# Teensy_FrequencyShield_2ch_slim.net
KiCad netlist of a schematic drawn in EAGLE
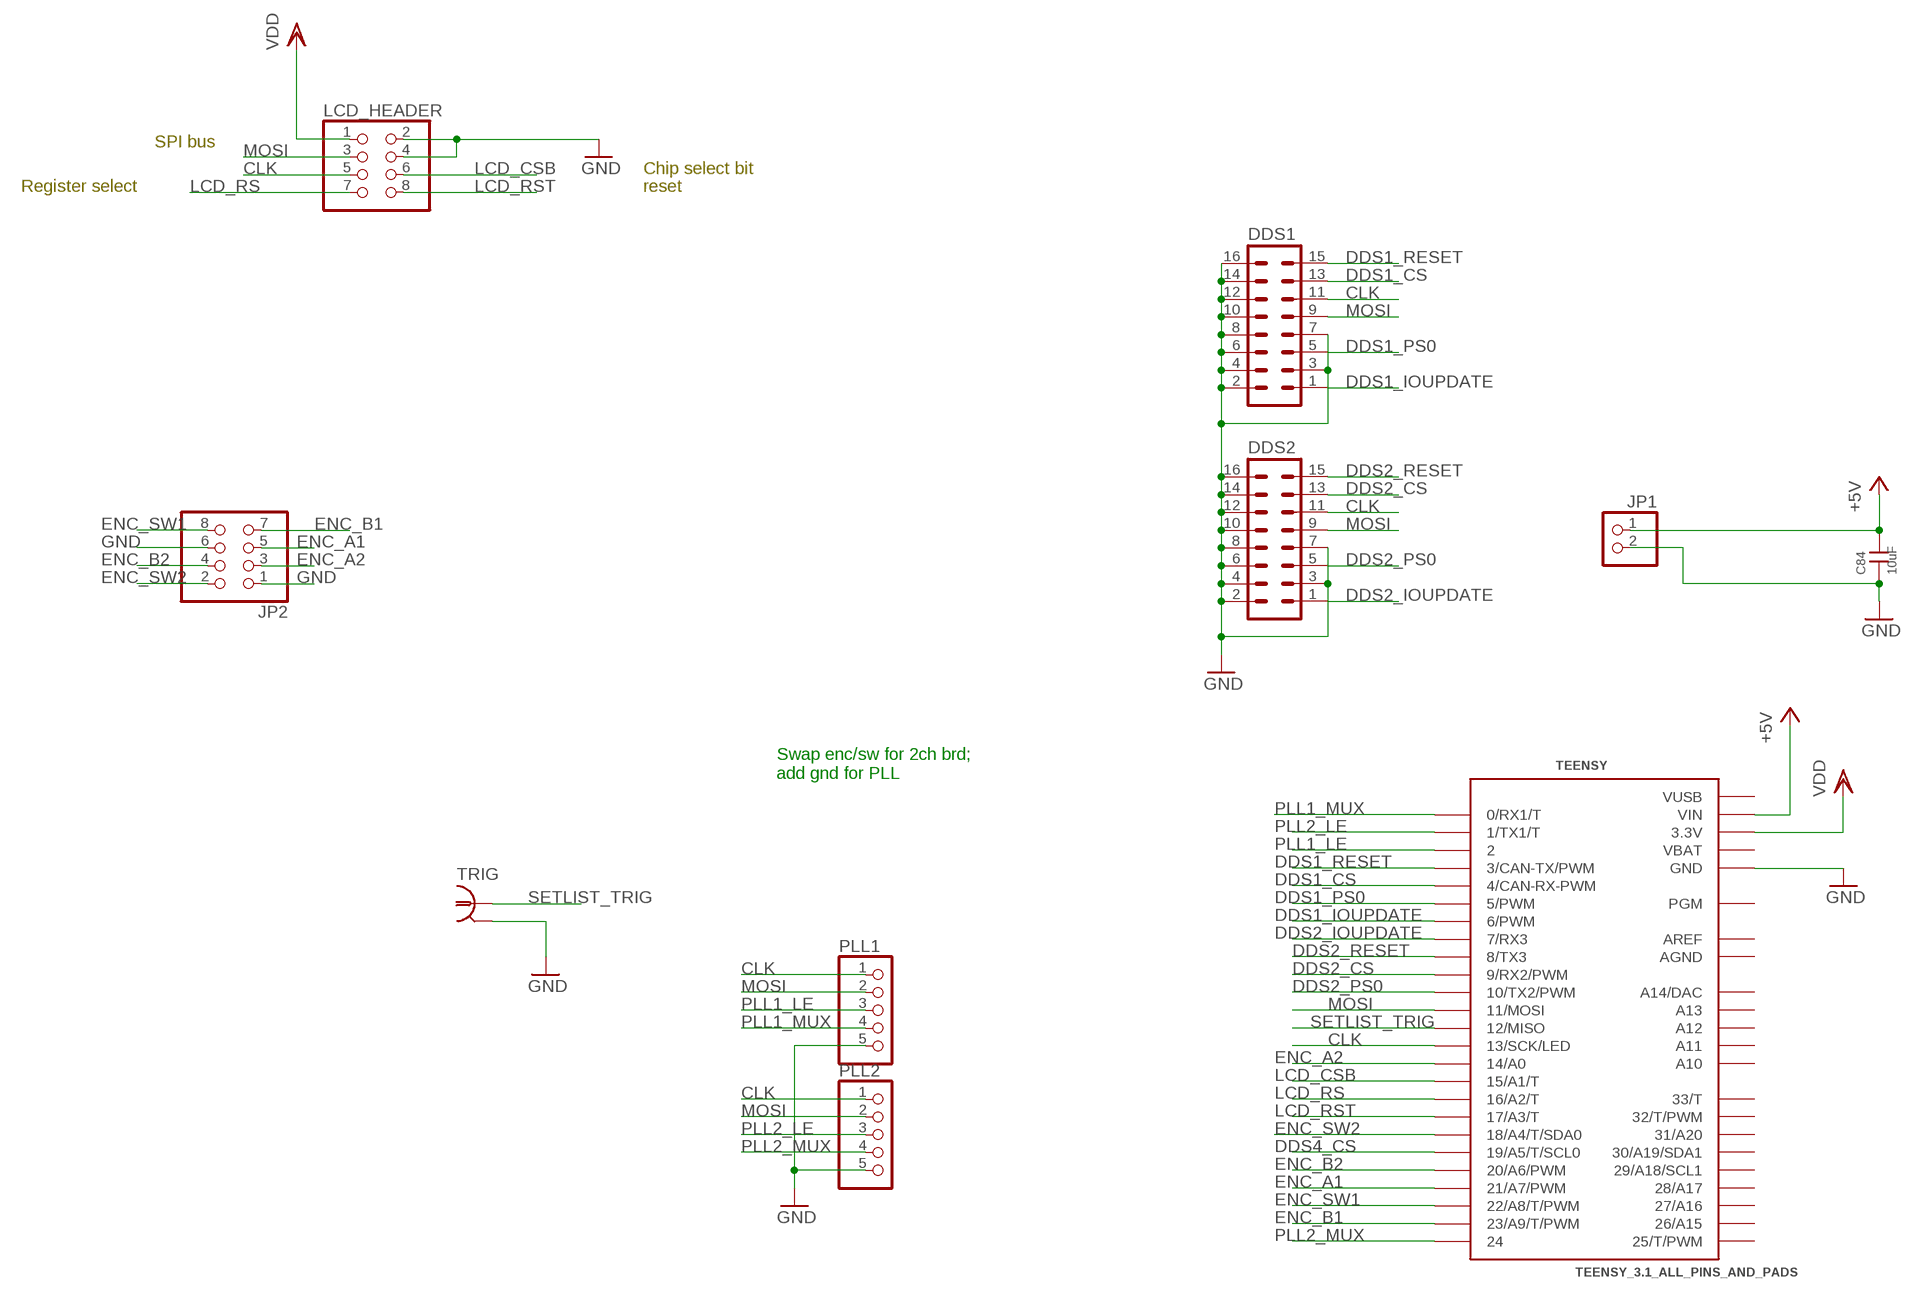
[diagram p0: schematic, sheet 1]

(export (version "E")
  (design (tool "Eeschema 10.0.6"))
  (components
    (comp (ref "C84")
      (value "10uF")
      (footprint "eagle-import:0805")
      (fields (field (name "PARTNO") "1276-2890-1-ND"))
      (libsource (lib "eagle-import") (part "CAP0805"))
    )
    (comp (ref "DDS1")
      (value "ML16")
      (footprint "eagle-import:ML16")
      (libsource (lib "eagle-import") (part "ML16"))
    )
    (comp (ref "DDS2")
      (value "ML16")
      (footprint "eagle-import:ML16")
      (libsource (lib "eagle-import") (part "ML16"))
    )
    (comp (ref "JP1")
      (value "PINHD-1X2")
      (footprint "eagle-import:1X02")
      (libsource (lib "eagle-import") (part "PINHD-1X2"))
    )
    (comp (ref "JP2")
      (value "PINHD-2X4-SHROUD")
      (footprint "eagle-import:ML08")
      (libsource (lib "eagle-import") (part "PINHD-2X4-SHROUD"))
    )
    (comp (ref "LCD_HEADER")
      (value "PINHD-2X4-SHROUD")
      (footprint "eagle-import:ML08")
      (libsource (lib "eagle-import") (part "PINHD-2X4-SHROUD"))
    )
    (comp (ref "PLL1")
      (value "PINHD-1X5")
      (footprint "eagle-import:1X05")
      (libsource (lib "eagle-import") (part "PINHD-1X5"))
    )
    (comp (ref "PLL2")
      (value "PINHD-1X5")
      (footprint "eagle-import:1X05")
      (libsource (lib "eagle-import") (part "PINHD-1X5"))
    )
    (comp (ref "TEENSY")
      (value "TEENSY_3.1_ALL_PINS_AND_PADS")
      (footprint "eagle-import:TEENSY_3.1_ALLPINS")
      (libsource (lib "eagle-import") (part "TEENSY_3.1_ALL_PINS_AND_PADS"))
    )
    (comp (ref "TRIG")
      (value "BNC-H")
      (footprint "eagle-import:BNC90")
      (libsource (lib "eagle-import") (part "BNC-H"))
    )
  )
  (nets
    (net (code "1") (name "+5V") (class "Default")
      (node (ref "C84") (pin "2") (pinfunction "P$2_2") (pintype "passive"))
      (node (ref "JP1") (pin "1") (pinfunction "1_1") (pintype "passive"))
      (node (ref "TEENSY") (pin "VIN") (pinfunction "VIN_VIN") (pintype "power_in"))
    )
    (net (code "2") (name "/AGND") (class "Default")
      (node (ref "TEENSY") (pin "AGND") (pinfunction "AGND_AGND") (pintype "power_in"))
    )
    (net (code "3") (name "/AREF") (class "Default")
      (node (ref "TEENSY") (pin "AREF") (pinfunction "AREF_AREF") (pintype "power_in"))
    )
    (net (code "4") (name "/CLK") (class "Default")
      (node (ref "DDS1") (pin "11") (pinfunction "11_11") (pintype "passive"))
      (node (ref "DDS2") (pin "11") (pinfunction "11_11") (pintype "passive"))
      (node (ref "LCD_HEADER") (pin "5") (pinfunction "5_5") (pintype "passive"))
      (node (ref "PLL1") (pin "1") (pinfunction "1_1") (pintype "passive"))
      (node (ref "PLL2") (pin "1") (pinfunction "1_1") (pintype "passive"))
      (node (ref "TEENSY") (pin "13") (pinfunction "13/SCK/LED_13") (pintype "bidirectional"))
    )
    (net (code "5") (name "/DDS1_CS") (class "Default")
      (node (ref "DDS1") (pin "13") (pinfunction "13_13") (pintype "passive"))
      (node (ref "TEENSY") (pin "4") (pinfunction "4/CAN-RX-PWM_4") (pintype "bidirectional"))
    )
    (net (code "6") (name "/DDS1_IOUPDATE") (class "Default")
      (node (ref "DDS1") (pin "1") (pinfunction "1_1") (pintype "passive"))
      (node (ref "TEENSY") (pin "6") (pinfunction "6/PWM_6") (pintype "bidirectional"))
    )
    (net (code "7") (name "/DDS1_PS0") (class "Default")
      (node (ref "DDS1") (pin "5") (pinfunction "5_5") (pintype "passive"))
      (node (ref "TEENSY") (pin "5") (pinfunction "5/PWM_5") (pintype "bidirectional"))
    )
    (net (code "8") (name "/DDS1_RESET") (class "Default")
      (node (ref "DDS1") (pin "15") (pinfunction "15_15") (pintype "passive"))
      (node (ref "TEENSY") (pin "3") (pinfunction "3/CAN-TX/PWM_3") (pintype "bidirectional"))
    )
    (net (code "9") (name "/DDS2_CS") (class "Default")
      (node (ref "DDS2") (pin "13") (pinfunction "13_13") (pintype "passive"))
      (node (ref "TEENSY") (pin "9") (pinfunction "9/RX2/PWM_9") (pintype "bidirectional"))
    )
    (net (code "10") (name "/DDS2_IOUPDATE") (class "Default")
      (node (ref "DDS2") (pin "1") (pinfunction "1_1") (pintype "passive"))
      (node (ref "TEENSY") (pin "7") (pinfunction "7/RX3_7") (pintype "bidirectional"))
    )
    (net (code "11") (name "/DDS2_PS0") (class "Default")
      (node (ref "DDS2") (pin "5") (pinfunction "5_5") (pintype "passive"))
      (node (ref "TEENSY") (pin "10") (pinfunction "10/TX2/PWM_10") (pintype "bidirectional"))
    )
    (net (code "12") (name "/DDS2_RESET") (class "Default")
      (node (ref "DDS2") (pin "15") (pinfunction "15_15") (pintype "passive"))
      (node (ref "TEENSY") (pin "8") (pinfunction "8/TX3_8") (pintype "bidirectional"))
    )
    (net (code "13") (name "/DDS4_CS") (class "Default")
      (node (ref "TEENSY") (pin "19/A5") (pinfunction "19/A5/T/SCL0_19/A5") (pintype "bidirectional"))
    )
    (net (code "14") (name "/ENC_A1") (class "Default")
      (node (ref "JP2") (pin "5") (pinfunction "5_5") (pintype "passive"))
      (node (ref "TEENSY") (pin "21/A7") (pinfunction "21/A7/PWM_21/A7") (pintype "bidirectional"))
    )
    (net (code "15") (name "/ENC_A2") (class "Default")
      (node (ref "JP2") (pin "3") (pinfunction "3_3") (pintype "passive"))
      (node (ref "TEENSY") (pin "14/A0") (pinfunction "14/A0_14/A0") (pintype "bidirectional"))
    )
    (net (code "16") (name "/ENC_B1") (class "Default")
      (node (ref "JP2") (pin "7") (pinfunction "7_7") (pintype "passive"))
      (node (ref "TEENSY") (pin "23/A9") (pinfunction "23/A9/T/PWM_23/A9") (pintype "bidirectional"))
    )
    (net (code "17") (name "/ENC_B2") (class "Default")
      (node (ref "JP2") (pin "4") (pinfunction "4_4") (pintype "passive"))
      (node (ref "TEENSY") (pin "20/A6") (pinfunction "20/A6/PWM_20/A6") (pintype "bidirectional"))
    )
    (net (code "18") (name "/ENC_SW1") (class "Default")
      (node (ref "JP2") (pin "8") (pinfunction "8_8") (pintype "passive"))
      (node (ref "TEENSY") (pin "22/A8") (pinfunction "22/A8/T/PWM_22/A8") (pintype "bidirectional"))
    )
    (net (code "19") (name "/ENC_SW2") (class "Default")
      (node (ref "JP2") (pin "2") (pinfunction "2_2") (pintype "passive"))
      (node (ref "TEENSY") (pin "18/A4") (pinfunction "18/A4/T/SDA0_18/A4") (pintype "bidirectional"))
    )
    (net (code "20") (name "/LCD_CSB") (class "Default")
      (node (ref "LCD_HEADER") (pin "6") (pinfunction "6_6") (pintype "passive"))
      (node (ref "TEENSY") (pin "15/A1") (pinfunction "15/A1/T_15/A1") (pintype "bidirectional"))
    )
    (net (code "21") (name "/LCD_RS") (class "Default")
      (node (ref "LCD_HEADER") (pin "7") (pinfunction "7_7") (pintype "passive"))
      (node (ref "TEENSY") (pin "16/A2") (pinfunction "16/A2/T_16/A2") (pintype "bidirectional"))
    )
    (net (code "22") (name "/LCD_RST") (class "Default")
      (node (ref "LCD_HEADER") (pin "8") (pinfunction "8_8") (pintype "passive"))
      (node (ref "TEENSY") (pin "17/A3") (pinfunction "17/A3/T_17/A3") (pintype "bidirectional"))
    )
    (net (code "23") (name "/MOSI") (class "Default")
      (node (ref "DDS1") (pin "9") (pinfunction "9_9") (pintype "passive"))
      (node (ref "DDS2") (pin "9") (pinfunction "9_9") (pintype "passive"))
      (node (ref "LCD_HEADER") (pin "3") (pinfunction "3_3") (pintype "passive"))
      (node (ref "PLL1") (pin "2") (pinfunction "2_2") (pintype "passive"))
      (node (ref "PLL2") (pin "2") (pinfunction "2_2") (pintype "passive"))
      (node (ref "TEENSY") (pin "11") (pinfunction "11/MOSI_11") (pintype "bidirectional"))
    )
    (net (code "24") (name "/PLL1_LE") (class "Default")
      (node (ref "PLL1") (pin "3") (pinfunction "3_3") (pintype "passive"))
      (node (ref "TEENSY") (pin "2") (pinfunction "2_2") (pintype "bidirectional"))
    )
    (net (code "25") (name "/PLL1_MUX") (class "Default")
      (node (ref "PLL1") (pin "4") (pinfunction "4_4") (pintype "passive"))
      (node (ref "TEENSY") (pin "0") (pinfunction "0/RX1/T_0") (pintype "bidirectional"))
    )
    (net (code "26") (name "/PLL2_LE") (class "Default")
      (node (ref "PLL2") (pin "3") (pinfunction "3_3") (pintype "passive"))
      (node (ref "TEENSY") (pin "1") (pinfunction "1/TX1/T_1") (pintype "bidirectional"))
    )
    (net (code "27") (name "/PLL2_MUX") (class "Default")
      (node (ref "PLL2") (pin "4") (pinfunction "4_4") (pintype "passive"))
      (node (ref "TEENSY") (pin "24") (pinfunction "24_24") (pintype "bidirectional"))
    )
    (net (code "28") (name "/SETLIST_TRIG") (class "Default")
      (node (ref "TEENSY") (pin "12") (pinfunction "12/MISO_12") (pintype "bidirectional"))
      (node (ref "TRIG") (pin "1") (pinfunction "1_1") (pintype "passive"))
    )
    (net (code "29") (name "/VBAT") (class "Default")
      (node (ref "TEENSY") (pin "VBAT") (pinfunction "VBAT_VBAT") (pintype "power_in"))
    )
    (net (code "30") (name "/VUSB") (class "Default")
      (node (ref "TEENSY") (pin "VUSB") (pinfunction "VUSB_VUSB") (pintype "power_in"))
    )
    (net (code "31") (name "GND") (class "Default")
      (node (ref "C84") (pin "1") (pinfunction "P$1_1") (pintype "passive"))
      (node (ref "DDS1") (pin "10") (pinfunction "10_10") (pintype "passive"))
      (node (ref "DDS1") (pin "12") (pinfunction "12_12") (pintype "passive"))
      (node (ref "DDS1") (pin "14") (pinfunction "14_14") (pintype "passive"))
      (node (ref "DDS1") (pin "16") (pinfunction "16_16") (pintype "passive"))
      (node (ref "DDS1") (pin "2") (pinfunction "2_2") (pintype "passive"))
      (node (ref "DDS1") (pin "3") (pinfunction "3_3") (pintype "passive"))
      (node (ref "DDS1") (pin "4") (pinfunction "4_4") (pintype "passive"))
      (node (ref "DDS1") (pin "6") (pinfunction "6_6") (pintype "passive"))
      (node (ref "DDS1") (pin "7") (pinfunction "7_7") (pintype "passive"))
      (node (ref "DDS1") (pin "8") (pinfunction "8_8") (pintype "passive"))
      (node (ref "DDS2") (pin "10") (pinfunction "10_10") (pintype "passive"))
      (node (ref "DDS2") (pin "12") (pinfunction "12_12") (pintype "passive"))
      (node (ref "DDS2") (pin "14") (pinfunction "14_14") (pintype "passive"))
      (node (ref "DDS2") (pin "16") (pinfunction "16_16") (pintype "passive"))
      (node (ref "DDS2") (pin "2") (pinfunction "2_2") (pintype "passive"))
      (node (ref "DDS2") (pin "3") (pinfunction "3_3") (pintype "passive"))
      (node (ref "DDS2") (pin "4") (pinfunction "4_4") (pintype "passive"))
      (node (ref "DDS2") (pin "6") (pinfunction "6_6") (pintype "passive"))
      (node (ref "DDS2") (pin "7") (pinfunction "7_7") (pintype "passive"))
      (node (ref "DDS2") (pin "8") (pinfunction "8_8") (pintype "passive"))
      (node (ref "JP1") (pin "2") (pinfunction "2_2") (pintype "passive"))
      (node (ref "JP2") (pin "1") (pinfunction "1_1") (pintype "passive"))
      (node (ref "JP2") (pin "6") (pinfunction "6_6") (pintype "passive"))
      (node (ref "LCD_HEADER") (pin "2") (pinfunction "2_2") (pintype "passive"))
      (node (ref "LCD_HEADER") (pin "4") (pinfunction "4_4") (pintype "passive"))
      (node (ref "PLL1") (pin "5") (pinfunction "5_5") (pintype "passive"))
      (node (ref "PLL2") (pin "5") (pinfunction "5_5") (pintype "passive"))
      (node (ref "TEENSY") (pin "GND") (pinfunction "GND_GND") (pintype "power_in"))
      (node (ref "TEENSY") (pin "GND1") (pinfunction "GND_GND1") (pintype "power_in"))
      (node (ref "TEENSY") (pin "GND2") (pinfunction "GND_GND2") (pintype "power_in"))
      (node (ref "TRIG") (pin "2") (pinfunction "2_2") (pintype "passive"))
    )
    (net (code "32") (name "VDD") (class "Default")
      (node (ref "LCD_HEADER") (pin "1") (pinfunction "1_1") (pintype "passive"))
      (node (ref "TEENSY") (pin "3.3V") (pinfunction "3.3V_3.3V") (pintype "power_in"))
      (node (ref "TEENSY") (pin "3.3V1") (pinfunction "3.3V_3.3V1") (pintype "power_in"))
      (node (ref "TEENSY") (pin "3.3V2") (pinfunction "3.3V_3.3V2") (pintype "power_in"))
    )
    (net (code "33") (name "unconnected-(TEENSY-25{slash}T{slash}PWM-Pad25)") (class "Default")
      (node (ref "TEENSY") (pin "25") (pinfunction "25/T/PWM_25") (pintype "bidirectional"))
    )
    (net (code "34") (name "unconnected-(TEENSY-26{slash}A15-Pad26)") (class "Default")
      (node (ref "TEENSY") (pin "26") (pinfunction "26/A15_26") (pintype "bidirectional"))
    )
    (net (code "35") (name "unconnected-(TEENSY-27{slash}A16-Pad27)") (class "Default")
      (node (ref "TEENSY") (pin "27") (pinfunction "27/A16_27") (pintype "bidirectional"))
    )
    (net (code "36") (name "unconnected-(TEENSY-28{slash}A17-Pad28)") (class "Default")
      (node (ref "TEENSY") (pin "28") (pinfunction "28/A17_28") (pintype "bidirectional"))
    )
    (net (code "37") (name "unconnected-(TEENSY-29{slash}A18{slash}SCL1-Pad29)") (class "Default")
      (node (ref "TEENSY") (pin "29") (pinfunction "29/A18/SCL1_29") (pintype "bidirectional"))
    )
    (net (code "38") (name "unconnected-(TEENSY-30{slash}A19{slash}SDA1-Pad30)") (class "Default")
      (node (ref "TEENSY") (pin "30") (pinfunction "30/A19/SDA1_30") (pintype "bidirectional"))
    )
    (net (code "39") (name "unconnected-(TEENSY-31{slash}A20-Pad31)") (class "Default")
      (node (ref "TEENSY") (pin "31") (pinfunction "31/A20_31") (pintype "bidirectional"))
    )
    (net (code "40") (name "unconnected-(TEENSY-32{slash}T{slash}PWM-Pad32)") (class "Default")
      (node (ref "TEENSY") (pin "32") (pinfunction "32/T/PWM_32") (pintype "bidirectional"))
    )
    (net (code "41") (name "unconnected-(TEENSY-33{slash}T-Pad33)") (class "Default")
      (node (ref "TEENSY") (pin "33") (pinfunction "33/T_33") (pintype "bidirectional"))
    )
    (net (code "42") (name "unconnected-(TEENSY-A14{slash}DAC-PadA14)") (class "Default")
      (node (ref "TEENSY") (pin "A14") (pinfunction "A14/DAC_A14") (pintype "bidirectional"))
    )
    (net (code "43") (name "unconnected-(TEENSY-PadA10)") (class "Default")
      (node (ref "TEENSY") (pin "A10") (pinfunction "A10_A10") (pintype "bidirectional"))
    )
    (net (code "44") (name "unconnected-(TEENSY-PadA11)") (class "Default")
      (node (ref "TEENSY") (pin "A11") (pinfunction "A11_A11") (pintype "bidirectional"))
    )
    (net (code "45") (name "unconnected-(TEENSY-PadA12)") (class "Default")
      (node (ref "TEENSY") (pin "A12") (pinfunction "A12_A12") (pintype "bidirectional"))
    )
    (net (code "46") (name "unconnected-(TEENSY-PadA13)") (class "Default")
      (node (ref "TEENSY") (pin "A13") (pinfunction "A13_A13") (pintype "bidirectional"))
    )
    (net (code "47") (name "unconnected-(TEENSY-PadPGM)") (class "Default")
      (node (ref "TEENSY") (pin "PGM") (pinfunction "PGM_PGM") (pintype "bidirectional"))
    )
  )
)
